# BSPD.net
KiCad netlist of a schematic drawn in EAGLE
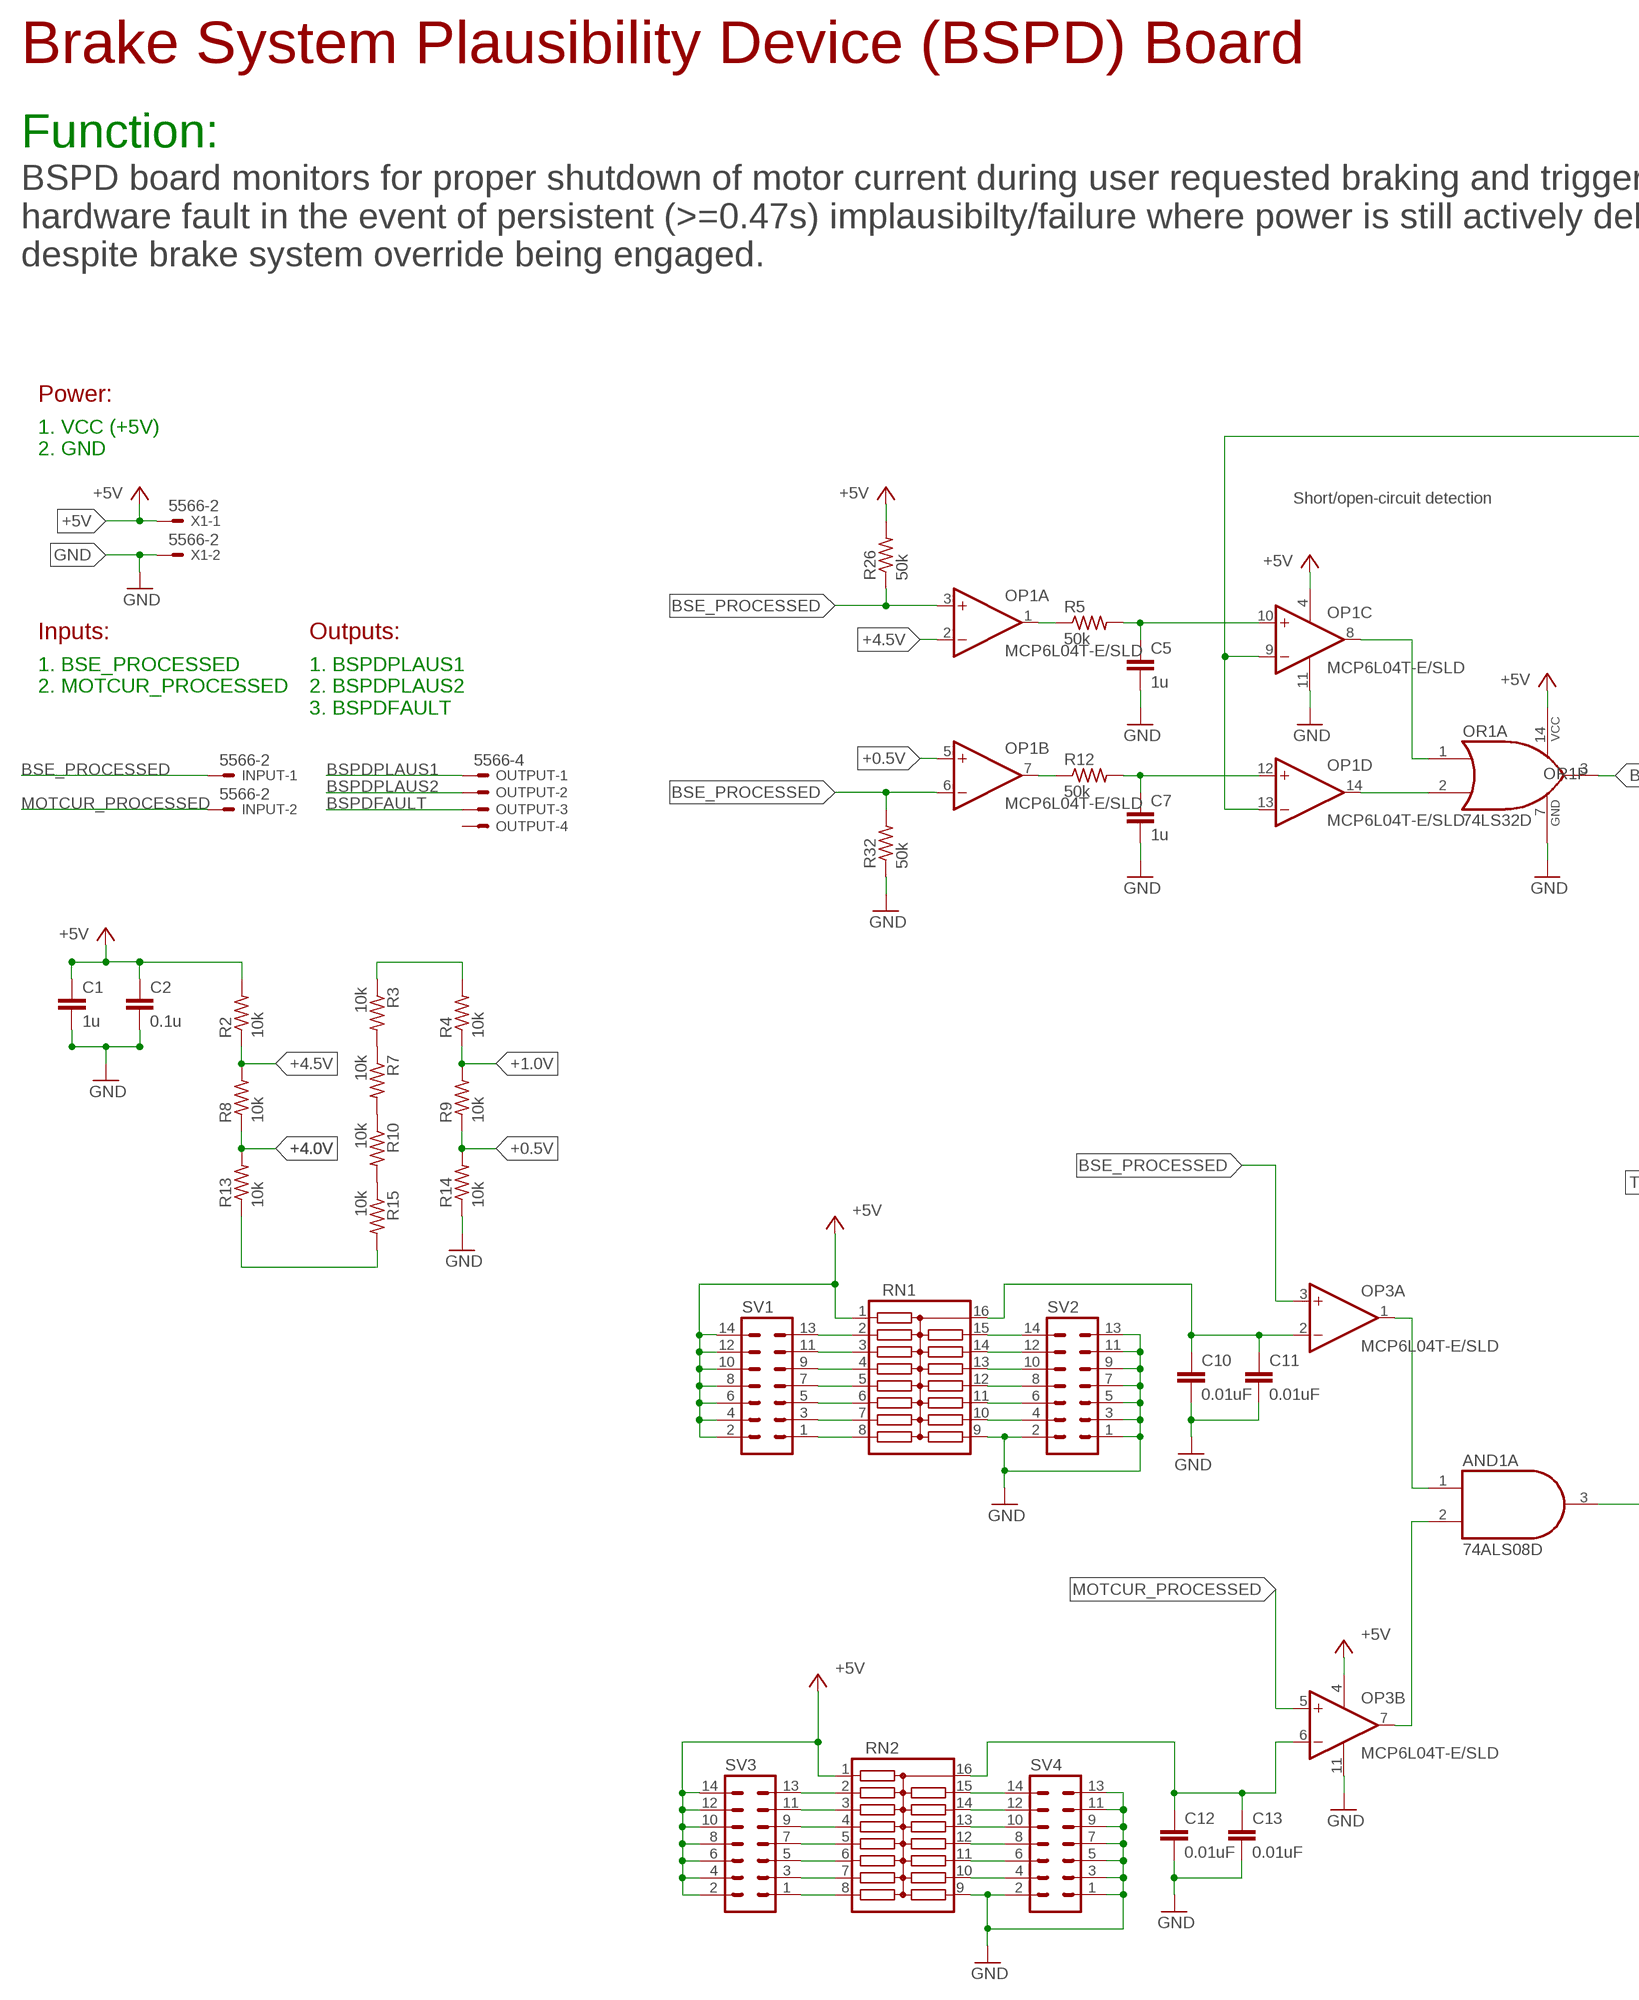
[diagram p0: schematic, sheet 1, part 1 of 2]
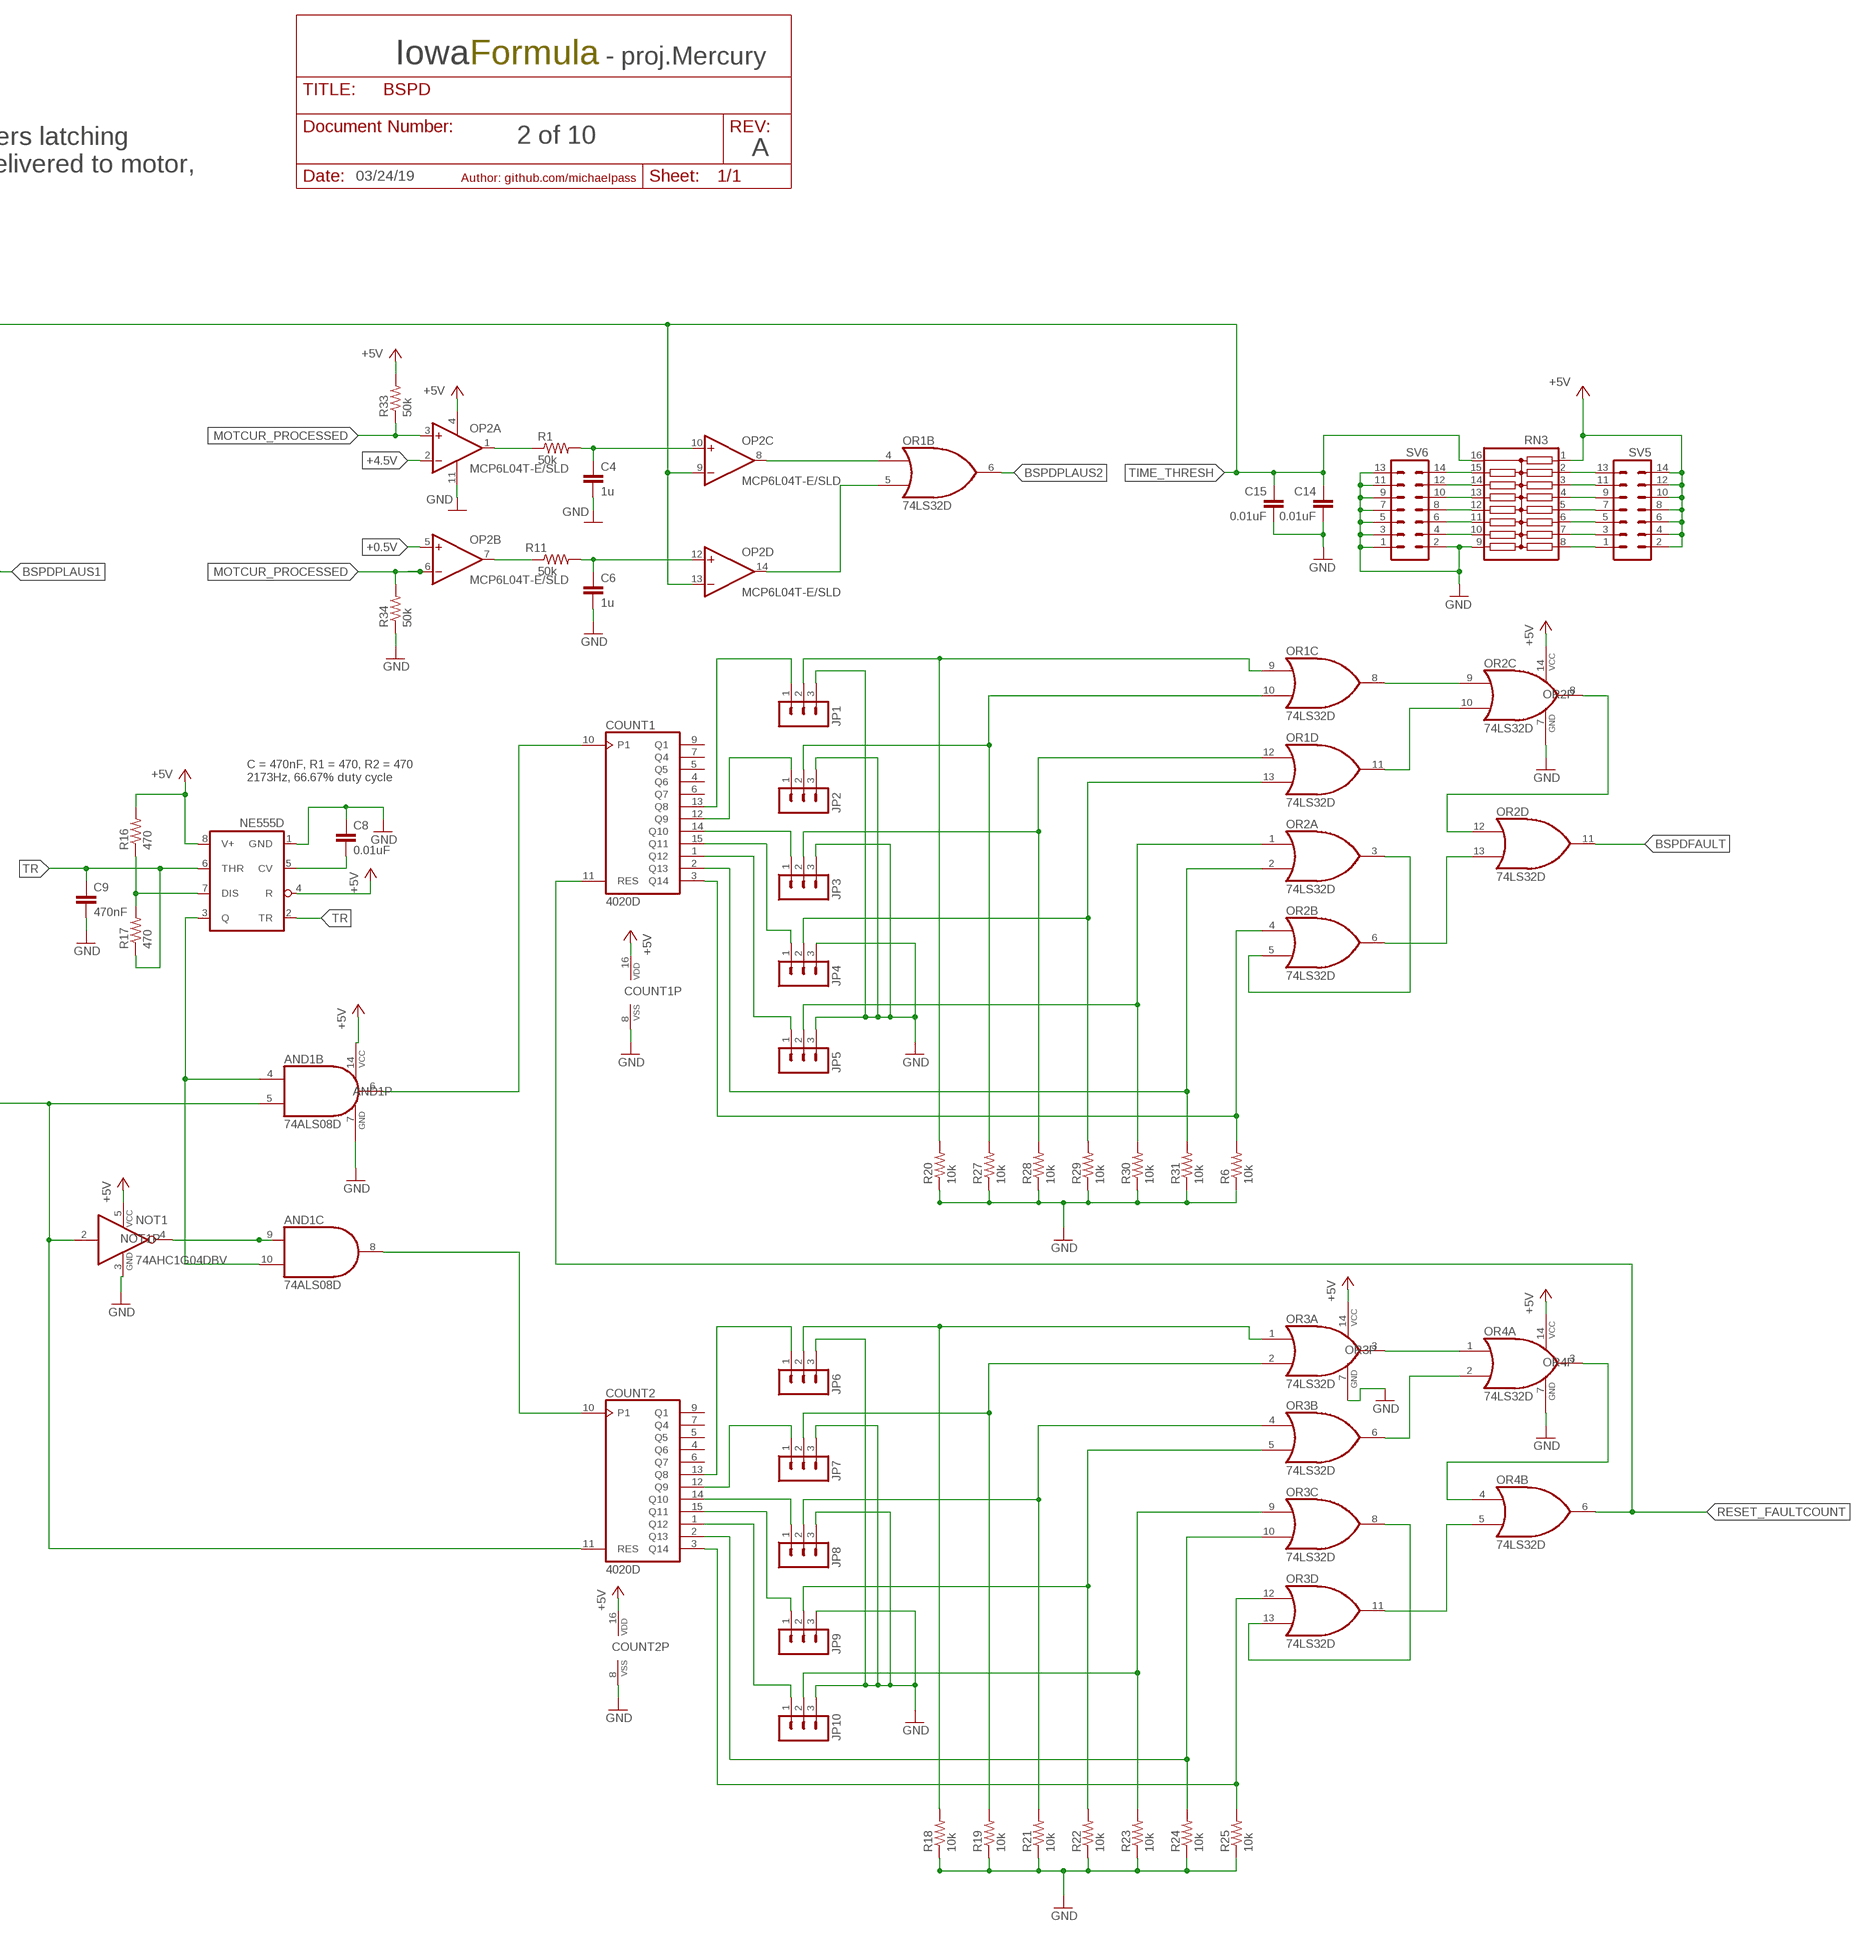
[diagram p1: schematic, sheet 1, part 2 of 2]

(export (version "E")
  (design (tool "Eeschema 10.0.6"))
  (components
    (comp (ref "AND1")
      (value "74ALS08D")
      (footprint "eagle-import:SO14")
      (libsource (lib "eagle-import") (part "7408DALS"))
    )
    (comp (ref "C1")
      (value "1u")
      (footprint "eagle-import:C0805")
      (libsource (lib "eagle-import") (part "C-EUC0805"))
    )
    (comp (ref "C2")
      (value "0.1u")
      (footprint "eagle-import:C0805")
      (libsource (lib "eagle-import") (part "C-EUC0805"))
    )
    (comp (ref "C4")
      (value "1u")
      (footprint "eagle-import:C0805")
      (libsource (lib "eagle-import") (part "C-EUC0805"))
    )
    (comp (ref "C5")
      (value "1u")
      (footprint "eagle-import:C0805")
      (libsource (lib "eagle-import") (part "C-EUC0805"))
    )
    (comp (ref "C6")
      (value "1u")
      (footprint "eagle-import:C0805")
      (libsource (lib "eagle-import") (part "C-EUC0805"))
    )
    (comp (ref "C7")
      (value "1u")
      (footprint "eagle-import:C0805")
      (libsource (lib "eagle-import") (part "C-EUC0805"))
    )
    (comp (ref "C8")
      (value "0.01uF")
      (footprint "eagle-import:C0805")
      (libsource (lib "eagle-import") (part "C-EUC0805"))
    )
    (comp (ref "C9")
      (value "470nF")
      (footprint "eagle-import:C0805")
      (libsource (lib "eagle-import") (part "C-EUC0805"))
    )
    (comp (ref "C10")
      (value "0.01uF")
      (footprint "eagle-import:C0805")
      (libsource (lib "eagle-import") (part "C-EUC0805"))
    )
    (comp (ref "C11")
      (value "0.01uF")
      (footprint "eagle-import:C0805")
      (libsource (lib "eagle-import") (part "C-EUC0805"))
    )
    (comp (ref "C12")
      (value "0.01uF")
      (footprint "eagle-import:C0805")
      (libsource (lib "eagle-import") (part "C-EUC0805"))
    )
    (comp (ref "C13")
      (value "0.01uF")
      (footprint "eagle-import:C0805")
      (libsource (lib "eagle-import") (part "C-EUC0805"))
    )
    (comp (ref "C14")
      (value "0.01uF")
      (footprint "eagle-import:C0805")
      (libsource (lib "eagle-import") (part "C-EUC0805"))
    )
    (comp (ref "C15")
      (value "0.01uF")
      (footprint "eagle-import:C0805")
      (libsource (lib "eagle-import") (part "C-EUC0805"))
    )
    (comp (ref "COUNT1")
      (value "4020D")
      (footprint "eagle-import:SO16")
      (libsource (lib "eagle-import") (part "4020D"))
    )
    (comp (ref "COUNT2")
      (value "4020D")
      (footprint "eagle-import:SO16")
      (libsource (lib "eagle-import") (part "4020D"))
    )
    (comp (ref "INPUT")
      (value "5566-2")
      (footprint "eagle-import:5566-2")
      (fields (field (name "MF") "MOLEX"))
      (libsource (lib "eagle-import") (part "5566-2"))
    )
    (comp (ref "JP1")
      (value "MA03-1")
      (footprint "eagle-import:MA03-1")
      (libsource (lib "eagle-import") (part "MA03-1"))
    )
    (comp (ref "JP2")
      (value "MA03-1")
      (footprint "eagle-import:MA03-1")
      (libsource (lib "eagle-import") (part "MA03-1"))
    )
    (comp (ref "JP3")
      (value "MA03-1")
      (footprint "eagle-import:MA03-1")
      (libsource (lib "eagle-import") (part "MA03-1"))
    )
    (comp (ref "JP4")
      (value "MA03-1")
      (footprint "eagle-import:MA03-1")
      (libsource (lib "eagle-import") (part "MA03-1"))
    )
    (comp (ref "JP5")
      (value "MA03-1")
      (footprint "eagle-import:MA03-1")
      (libsource (lib "eagle-import") (part "MA03-1"))
    )
    (comp (ref "JP6")
      (value "MA03-1")
      (footprint "eagle-import:MA03-1")
      (libsource (lib "eagle-import") (part "MA03-1"))
    )
    (comp (ref "JP7")
      (value "MA03-1")
      (footprint "eagle-import:MA03-1")
      (libsource (lib "eagle-import") (part "MA03-1"))
    )
    (comp (ref "JP8")
      (value "MA03-1")
      (footprint "eagle-import:MA03-1")
      (libsource (lib "eagle-import") (part "MA03-1"))
    )
    (comp (ref "JP9")
      (value "MA03-1")
      (footprint "eagle-import:MA03-1")
      (libsource (lib "eagle-import") (part "MA03-1"))
    )
    (comp (ref "JP10")
      (value "MA03-1")
      (footprint "eagle-import:MA03-1")
      (libsource (lib "eagle-import") (part "MA03-1"))
    )
    (comp (ref "NE555D")
      (value "NE555D")
      (footprint "eagle-import:SO08")
      (libsource (lib "eagle-import") (part "555DNE"))
    )
    (comp (ref "NOT1")
      (value "74AHC1G04DBV")
      (footprint "eagle-import:SOT23-5")
      (libsource (lib "eagle-import") (part "741G04DBVAHC"))
    )
    (comp (ref "OP1")
      (value "MCP6L04T-E/SLD")
      (footprint "eagle-import:SO14")
      (libsource (lib "eagle-import") (part "MCP6L04T-E/SLD"))
    )
    (comp (ref "OP2")
      (value "MCP6L04T-E/SLD")
      (footprint "eagle-import:SO14")
      (libsource (lib "eagle-import") (part "MCP6L04T-E/SLD"))
    )
    (comp (ref "OP3")
      (value "MCP6L04T-E/SLD")
      (footprint "eagle-import:SO14")
      (libsource (lib "eagle-import") (part "MCP6L04T-E/SLD"))
    )
    (comp (ref "OR1")
      (value "74LS32D")
      (footprint "eagle-import:SO14")
      (fields (field (name "SPICEPREFIX") "J"))
      (libsource (lib "eagle-import") (part "7432DLS"))
    )
    (comp (ref "OR2")
      (value "74LS32D")
      (footprint "eagle-import:SO14")
      (libsource (lib "eagle-import") (part "7432DLS"))
    )
    (comp (ref "OR3")
      (value "74LS32D")
      (footprint "eagle-import:SO14")
      (libsource (lib "eagle-import") (part "7432DLS"))
    )
    (comp (ref "OR4")
      (value "74LS32D")
      (footprint "eagle-import:SO14")
      (libsource (lib "eagle-import") (part "7432DLS"))
    )
    (comp (ref "OUTPUT")
      (value "5566-4")
      (footprint "eagle-import:5566-4")
      (fields (field (name "MF") "MOLEX"))
      (libsource (lib "eagle-import") (part "5566-4"))
    )
    (comp (ref "R1")
      (value "50k")
      (footprint "eagle-import:R0805")
      (libsource (lib "eagle-import") (part "R-US_R0805"))
    )
    (comp (ref "R2")
      (value "10k")
      (footprint "eagle-import:R0805")
      (libsource (lib "eagle-import") (part "R-US_R0805"))
    )
    (comp (ref "R3")
      (value "10k")
      (footprint "eagle-import:R0805")
      (libsource (lib "eagle-import") (part "R-US_R0805"))
    )
    (comp (ref "R4")
      (value "10k")
      (footprint "eagle-import:R0805")
      (libsource (lib "eagle-import") (part "R-US_R0805"))
    )
    (comp (ref "R5")
      (value "50k")
      (footprint "eagle-import:R0805")
      (libsource (lib "eagle-import") (part "R-US_R0805"))
    )
    (comp (ref "R6")
      (value "10k")
      (footprint "eagle-import:R0805")
      (libsource (lib "eagle-import") (part "R-US_R0805"))
    )
    (comp (ref "R7")
      (value "10k")
      (footprint "eagle-import:R0805")
      (libsource (lib "eagle-import") (part "R-US_R0805"))
    )
    (comp (ref "R8")
      (value "10k")
      (footprint "eagle-import:R0805")
      (libsource (lib "eagle-import") (part "R-US_R0805"))
    )
    (comp (ref "R9")
      (value "10k")
      (footprint "eagle-import:R0805")
      (libsource (lib "eagle-import") (part "R-US_R0805"))
    )
    (comp (ref "R10")
      (value "10k")
      (footprint "eagle-import:R0805")
      (libsource (lib "eagle-import") (part "R-US_R0805"))
    )
    (comp (ref "R11")
      (value "50k")
      (footprint "eagle-import:R0805")
      (libsource (lib "eagle-import") (part "R-US_R0805"))
    )
    (comp (ref "R12")
      (value "50k")
      (footprint "eagle-import:R0805")
      (libsource (lib "eagle-import") (part "R-US_R0805"))
    )
    (comp (ref "R13")
      (value "10k")
      (footprint "eagle-import:R0805")
      (libsource (lib "eagle-import") (part "R-US_R0805"))
    )
    (comp (ref "R14")
      (value "10k")
      (footprint "eagle-import:R0805")
      (libsource (lib "eagle-import") (part "R-US_R0805"))
    )
    (comp (ref "R15")
      (value "10k")
      (footprint "eagle-import:R0805")
      (libsource (lib "eagle-import") (part "R-US_R0805"))
    )
    (comp (ref "R16")
      (value "470")
      (footprint "eagle-import:R0805")
      (libsource (lib "eagle-import") (part "R-US_R0805"))
    )
    (comp (ref "R17")
      (value "470")
      (footprint "eagle-import:R0805")
      (libsource (lib "eagle-import") (part "R-US_R0805"))
    )
    (comp (ref "R18")
      (value "10k")
      (footprint "eagle-import:R0805")
      (libsource (lib "eagle-import") (part "R-US_R0805"))
    )
    (comp (ref "R19")
      (value "10k")
      (footprint "eagle-import:R0805")
      (libsource (lib "eagle-import") (part "R-US_R0805"))
    )
    (comp (ref "R20")
      (value "10k")
      (footprint "eagle-import:R0805")
      (libsource (lib "eagle-import") (part "R-US_R0805"))
    )
    (comp (ref "R21")
      (value "10k")
      (footprint "eagle-import:R0805")
      (libsource (lib "eagle-import") (part "R-US_R0805"))
    )
    (comp (ref "R22")
      (value "10k")
      (footprint "eagle-import:R0805")
      (libsource (lib "eagle-import") (part "R-US_R0805"))
    )
    (comp (ref "R23")
      (value "10k")
      (footprint "eagle-import:R0805")
      (libsource (lib "eagle-import") (part "R-US_R0805"))
    )
    (comp (ref "R24")
      (value "10k")
      (footprint "eagle-import:R0805")
      (libsource (lib "eagle-import") (part "R-US_R0805"))
    )
    (comp (ref "R25")
      (value "10k")
      (footprint "eagle-import:R0805")
      (libsource (lib "eagle-import") (part "R-US_R0805"))
    )
    (comp (ref "R26")
      (value "50k")
      (footprint "eagle-import:R0805")
      (libsource (lib "eagle-import") (part "R-US_R0805"))
    )
    (comp (ref "R27")
      (value "10k")
      (footprint "eagle-import:R0805")
      (libsource (lib "eagle-import") (part "R-US_R0805"))
    )
    (comp (ref "R28")
      (value "10k")
      (footprint "eagle-import:R0805")
      (libsource (lib "eagle-import") (part "R-US_R0805"))
    )
    (comp (ref "R29")
      (value "10k")
      (footprint "eagle-import:R0805")
      (libsource (lib "eagle-import") (part "R-US_R0805"))
    )
    (comp (ref "R30")
      (value "10k")
      (footprint "eagle-import:R0805")
      (libsource (lib "eagle-import") (part "R-US_R0805"))
    )
    (comp (ref "R31")
      (value "10k")
      (footprint "eagle-import:R0805")
      (libsource (lib "eagle-import") (part "R-US_R0805"))
    )
    (comp (ref "R32")
      (value "50k")
      (footprint "eagle-import:R0805")
      (libsource (lib "eagle-import") (part "R-US_R0805"))
    )
    (comp (ref "R33")
      (value "50k")
      (footprint "eagle-import:R0805")
      (libsource (lib "eagle-import") (part "R-US_R0805"))
    )
    (comp (ref "R34")
      (value "50k")
      (footprint "eagle-import:R0805")
      (libsource (lib "eagle-import") (part "R-US_R0805"))
    )
    (comp (ref "RN1")
      (value "15RSOMC")
      (footprint "eagle-import:SOMC16")
      (fields (field (name "MPN") "SOMC160115R0GDC"))
      (libsource (lib "eagle-import") (part "15RSOMC"))
    )
    (comp (ref "RN2")
      (value "15RSOMC")
      (footprint "eagle-import:SOMC16")
      (fields (field (name "MPN") "SOMC160115R0GDC"))
      (libsource (lib "eagle-import") (part "15RSOMC"))
    )
    (comp (ref "RN3")
      (value "15RSOMC")
      (footprint "eagle-import:SOMC16")
      (fields (field (name "MPN") "SOMC160115R0GDC"))
      (libsource (lib "eagle-import") (part "15RSOMC"))
    )
    (comp (ref "SV1")
      (value "MA07-2")
      (footprint "eagle-import:MA07-2")
      (libsource (lib "eagle-import") (part "MA07-2"))
    )
    (comp (ref "SV2")
      (value "MA07-2")
      (footprint "eagle-import:MA07-2")
      (libsource (lib "eagle-import") (part "MA07-2"))
    )
    (comp (ref "SV3")
      (value "MA07-2")
      (footprint "eagle-import:MA07-2")
      (libsource (lib "eagle-import") (part "MA07-2"))
    )
    (comp (ref "SV4")
      (value "MA07-2")
      (footprint "eagle-import:MA07-2")
      (libsource (lib "eagle-import") (part "MA07-2"))
    )
    (comp (ref "SV5")
      (value "MA07-2")
      (footprint "eagle-import:MA07-2")
      (libsource (lib "eagle-import") (part "MA07-2"))
    )
    (comp (ref "SV6")
      (value "MA07-2")
      (footprint "eagle-import:MA07-2")
      (libsource (lib "eagle-import") (part "MA07-2"))
    )
    (comp (ref "X1")
      (value "5566-2")
      (footprint "eagle-import:5566-2")
      (fields (field (name "MF") "MOLEX"))
      (libsource (lib "eagle-import") (part "5566-2"))
    )
  )
  (nets
    (net (code "1") (name "+0.5V") (class "Default")
      (node (ref "OP1") (pin "5") (pinfunction "+IN_5") (pintype "input"))
      (node (ref "OP2") (pin "5") (pinfunction "+IN_5") (pintype "input"))
      (node (ref "R14") (pin "2") (pinfunction "2_2") (pintype "passive"))
      (node (ref "R9") (pin "1") (pinfunction "1_1") (pintype "passive"))
    )
    (net (code "2") (name "+1.0V") (class "Default")
      (node (ref "R4") (pin "1") (pinfunction "1_1") (pintype "passive"))
      (node (ref "R9") (pin "2") (pinfunction "2_2") (pintype "passive"))
    )
    (net (code "3") (name "+4.0V") (class "Default")
      (node (ref "R13") (pin "2") (pinfunction "2_2") (pintype "passive"))
      (node (ref "R8") (pin "1") (pinfunction "1_1") (pintype "passive"))
    )
    (net (code "4") (name "+4.5V") (class "Default")
      (node (ref "OP1") (pin "2") (pinfunction "-IN_2") (pintype "input"))
      (node (ref "OP2") (pin "2") (pinfunction "-IN_2") (pintype "input"))
      (node (ref "R2") (pin "1") (pinfunction "1_1") (pintype "passive"))
      (node (ref "R8") (pin "2") (pinfunction "2_2") (pintype "passive"))
    )
    (net (code "5") (name "+5V") (class "Default")
      (node (ref "AND1") (pin "14") (pinfunction "VCC_14") (pintype "power_in"))
      (node (ref "C1") (pin "1") (pinfunction "1_1") (pintype "passive"))
      (node (ref "C2") (pin "1") (pinfunction "1_1") (pintype "passive"))
      (node (ref "COUNT1") (pin "16") (pinfunction "VDD_16") (pintype "power_in"))
      (node (ref "COUNT2") (pin "16") (pinfunction "VDD_16") (pintype "power_in"))
      (node (ref "NE555D") (pin "4") (pinfunction "R_4") (pintype "input"))
      (node (ref "NE555D") (pin "8") (pinfunction "V+_8") (pintype "power_in"))
      (node (ref "NOT1") (pin "5") (pinfunction "VCC_5") (pintype "power_in"))
      (node (ref "OP1") (pin "4") (pinfunction "V+_4") (pintype "power_in"))
      (node (ref "OP2") (pin "4") (pinfunction "V+_4") (pintype "power_in"))
      (node (ref "OP3") (pin "4") (pinfunction "V+_4") (pintype "power_in"))
      (node (ref "OR1") (pin "14") (pinfunction "VCC_14") (pintype "power_in"))
      (node (ref "OR2") (pin "14") (pinfunction "VCC_14") (pintype "power_in"))
      (node (ref "OR3") (pin "14") (pinfunction "VCC_14") (pintype "power_in"))
      (node (ref "OR4") (pin "14") (pinfunction "VCC_14") (pintype "power_in"))
      (node (ref "R16") (pin "2") (pinfunction "2_2") (pintype "passive"))
      (node (ref "R2") (pin "2") (pinfunction "2_2") (pintype "passive"))
      (node (ref "R26") (pin "2") (pinfunction "2_2") (pintype "passive"))
      (node (ref "R33") (pin "2") (pinfunction "2_2") (pintype "passive"))
      (node (ref "RN1") (pin "1") (pinfunction "1_1") (pintype "passive"))
      (node (ref "RN2") (pin "1") (pinfunction "1_1") (pintype "passive"))
      (node (ref "RN3") (pin "1") (pinfunction "1_1") (pintype "passive"))
      (node (ref "SV1") (pin "10") (pinfunction "10_10") (pintype "passive"))
      (node (ref "SV1") (pin "12") (pinfunction "12_12") (pintype "passive"))
      (node (ref "SV1") (pin "14") (pinfunction "14_14") (pintype "passive"))
      (node (ref "SV1") (pin "2") (pinfunction "2_2") (pintype "passive"))
      (node (ref "SV1") (pin "4") (pinfunction "4_4") (pintype "passive"))
      (node (ref "SV1") (pin "6") (pinfunction "6_6") (pintype "passive"))
      (node (ref "SV1") (pin "8") (pinfunction "8_8") (pintype "passive"))
      (node (ref "SV3") (pin "10") (pinfunction "10_10") (pintype "passive"))
      (node (ref "SV3") (pin "12") (pinfunction "12_12") (pintype "passive"))
      (node (ref "SV3") (pin "14") (pinfunction "14_14") (pintype "passive"))
      (node (ref "SV3") (pin "2") (pinfunction "2_2") (pintype "passive"))
      (node (ref "SV3") (pin "4") (pinfunction "4_4") (pintype "passive"))
      (node (ref "SV3") (pin "6") (pinfunction "6_6") (pintype "passive"))
      (node (ref "SV3") (pin "8") (pinfunction "8_8") (pintype "passive"))
      (node (ref "SV5") (pin "10") (pinfunction "10_10") (pintype "passive"))
      (node (ref "SV5") (pin "12") (pinfunction "12_12") (pintype "passive"))
      (node (ref "SV5") (pin "14") (pinfunction "14_14") (pintype "passive"))
      (node (ref "SV5") (pin "2") (pinfunction "2_2") (pintype "passive"))
      (node (ref "SV5") (pin "4") (pinfunction "4_4") (pintype "passive"))
      (node (ref "SV5") (pin "6") (pinfunction "6_6") (pintype "passive"))
      (node (ref "SV5") (pin "8") (pinfunction "8_8") (pintype "passive"))
      (node (ref "X1") (pin "1") (pinfunction "S_1") (pintype "passive"))
    )
    (net (code "6") (name "BSE_PROCESSED") (class "Default")
      (node (ref "INPUT") (pin "1") (pinfunction "S_1") (pintype "passive"))
      (node (ref "OP1") (pin "3") (pinfunction "+IN_3") (pintype "input"))
      (node (ref "OP1") (pin "6") (pinfunction "-IN_6") (pintype "input"))
      (node (ref "OP3") (pin "3") (pinfunction "+IN_3") (pintype "input"))
      (node (ref "R26") (pin "1") (pinfunction "1_1") (pintype "passive"))
      (node (ref "R32") (pin "2") (pinfunction "2_2") (pintype "passive"))
    )
    (net (code "7") (name "BSPDFAULT") (class "Default")
      (node (ref "OR2") (pin "11") (pinfunction "O_11") (pintype "output"))
      (node (ref "OUTPUT") (pin "3") (pinfunction "S_3") (pintype "passive"))
    )
    (net (code "8") (name "BSPDPLAUS1") (class "Default")
      (node (ref "OR1") (pin "3") (pinfunction "O_3") (pintype "output"))
      (node (ref "OUTPUT") (pin "1") (pinfunction "S_1") (pintype "passive"))
    )
    (net (code "9") (name "BSPDPLAUS2") (class "Default")
      (node (ref "OR1") (pin "6") (pinfunction "O_6") (pintype "output"))
      (node (ref "OUTPUT") (pin "2") (pinfunction "S_2") (pintype "passive"))
    )
    (net (code "10") (name "GND") (class "Default")
      (node (ref "AND1") (pin "7") (pinfunction "GND_7") (pintype "power_in"))
      (node (ref "C1") (pin "2") (pinfunction "2_2") (pintype "passive"))
      (node (ref "C10") (pin "2") (pinfunction "2_2") (pintype "passive"))
      (node (ref "C11") (pin "2") (pinfunction "2_2") (pintype "passive"))
      (node (ref "C12") (pin "2") (pinfunction "2_2") (pintype "passive"))
      (node (ref "C13") (pin "2") (pinfunction "2_2") (pintype "passive"))
      (node (ref "C14") (pin "2") (pinfunction "2_2") (pintype "passive"))
      (node (ref "C15") (pin "2") (pinfunction "2_2") (pintype "passive"))
      (node (ref "C2") (pin "2") (pinfunction "2_2") (pintype "passive"))
      (node (ref "C4") (pin "2") (pinfunction "2_2") (pintype "passive"))
      (node (ref "C5") (pin "2") (pinfunction "2_2") (pintype "passive"))
      (node (ref "C6") (pin "2") (pinfunction "2_2") (pintype "passive"))
      (node (ref "C7") (pin "2") (pinfunction "2_2") (pintype "passive"))
      (node (ref "C8") (pin "1") (pinfunction "1_1") (pintype "passive"))
      (node (ref "C9") (pin "2") (pinfunction "2_2") (pintype "passive"))
      (node (ref "COUNT1") (pin "8") (pinfunction "VSS_8") (pintype "power_in"))
      (node (ref "COUNT2") (pin "8") (pinfunction "VSS_8") (pintype "power_in"))
      (node (ref "JP1") (pin "3") (pinfunction "3_3") (pintype "passive"))
      (node (ref "JP10") (pin "3") (pinfunction "3_3") (pintype "passive"))
      (node (ref "JP2") (pin "3") (pinfunction "3_3") (pintype "passive"))
      (node (ref "JP3") (pin "3") (pinfunction "3_3") (pintype "passive"))
      (node (ref "JP4") (pin "3") (pinfunction "3_3") (pintype "passive"))
      (node (ref "JP5") (pin "3") (pinfunction "3_3") (pintype "passive"))
      (node (ref "JP6") (pin "3") (pinfunction "3_3") (pintype "passive"))
      (node (ref "JP7") (pin "3") (pinfunction "3_3") (pintype "passive"))
      (node (ref "JP8") (pin "3") (pinfunction "3_3") (pintype "passive"))
      (node (ref "JP9") (pin "3") (pinfunction "3_3") (pintype "passive"))
      (node (ref "NE555D") (pin "1") (pinfunction "GND_1") (pintype "power_in"))
      (node (ref "NOT1") (pin "3") (pinfunction "GND_3") (pintype "power_in"))
      (node (ref "OP1") (pin "11") (pinfunction "V-_11") (pintype "power_in"))
      (node (ref "OP2") (pin "11") (pinfunction "V-_11") (pintype "power_in"))
      (node (ref "OP3") (pin "11") (pinfunction "V-_11") (pintype "power_in"))
      (node (ref "OR1") (pin "7") (pinfunction "GND_7") (pintype "power_in"))
      (node (ref "OR2") (pin "7") (pinfunction "GND_7") (pintype "power_in"))
      (node (ref "OR3") (pin "7") (pinfunction "GND_7") (pintype "power_in"))
      (node (ref "OR4") (pin "7") (pinfunction "GND_7") (pintype "power_in"))
      (node (ref "R14") (pin "1") (pinfunction "1_1") (pintype "passive"))
      (node (ref "R18") (pin "1") (pinfunction "1_1") (pintype "passive"))
      (node (ref "R19") (pin "1") (pinfunction "1_1") (pintype "passive"))
      (node (ref "R20") (pin "1") (pinfunction "1_1") (pintype "passive"))
      (node (ref "R21") (pin "1") (pinfunction "1_1") (pintype "passive"))
      (node (ref "R22") (pin "1") (pinfunction "1_1") (pintype "passive"))
      (node (ref "R23") (pin "1") (pinfunction "1_1") (pintype "passive"))
      (node (ref "R24") (pin "1") (pinfunction "1_1") (pintype "passive"))
      (node (ref "R25") (pin "1") (pinfunction "1_1") (pintype "passive"))
      (node (ref "R27") (pin "1") (pinfunction "1_1") (pintype "passive"))
      (node (ref "R28") (pin "1") (pinfunction "1_1") (pintype "passive"))
      (node (ref "R29") (pin "1") (pinfunction "1_1") (pintype "passive"))
      (node (ref "R30") (pin "1") (pinfunction "1_1") (pintype "passive"))
      (node (ref "R31") (pin "1") (pinfunction "1_1") (pintype "passive"))
      (node (ref "R32") (pin "1") (pinfunction "1_1") (pintype "passive"))
      (node (ref "R34") (pin "1") (pinfunction "1_1") (pintype "passive"))
      (node (ref "R6") (pin "1") (pinfunction "1_1") (pintype "passive"))
      (node (ref "RN1") (pin "9") (pinfunction "9_9") (pintype "passive"))
      (node (ref "RN2") (pin "9") (pinfunction "9_9") (pintype "passive"))
      (node (ref "RN3") (pin "9") (pinfunction "9_9") (pintype "passive"))
      (node (ref "SV2") (pin "1") (pinfunction "1_1") (pintype "passive"))
      (node (ref "SV2") (pin "11") (pinfunction "11_11") (pintype "passive"))
      (node (ref "SV2") (pin "13") (pinfunction "13_13") (pintype "passive"))
      (node (ref "SV2") (pin "2") (pinfunction "2_2") (pintype "passive"))
      (node (ref "SV2") (pin "3") (pinfunction "3_3") (pintype "passive"))
      (node (ref "SV2") (pin "5") (pinfunction "5_5") (pintype "passive"))
      (node (ref "SV2") (pin "7") (pinfunction "7_7") (pintype "passive"))
      (node (ref "SV2") (pin "9") (pinfunction "9_9") (pintype "passive"))
      (node (ref "SV4") (pin "1") (pinfunction "1_1") (pintype "passive"))
      (node (ref "SV4") (pin "11") (pinfunction "11_11") (pintype "passive"))
      (node (ref "SV4") (pin "13") (pinfunction "13_13") (pintype "passive"))
      (node (ref "SV4") (pin "2") (pinfunction "2_2") (pintype "passive"))
      (node (ref "SV4") (pin "3") (pinfunction "3_3") (pintype "passive"))
      (node (ref "SV4") (pin "5") (pinfunction "5_5") (pintype "passive"))
      (node (ref "SV4") (pin "7") (pinfunction "7_7") (pintype "passive"))
      (node (ref "SV4") (pin "9") (pinfunction "9_9") (pintype "passive"))
      (node (ref "SV6") (pin "1") (pinfunction "1_1") (pintype "passive"))
      (node (ref "SV6") (pin "11") (pinfunction "11_11") (pintype "passive"))
      (node (ref "SV6") (pin "13") (pinfunction "13_13") (pintype "passive"))
      (node (ref "SV6") (pin "2") (pinfunction "2_2") (pintype "passive"))
      (node (ref "SV6") (pin "3") (pinfunction "3_3") (pintype "passive"))
      (node (ref "SV6") (pin "5") (pinfunction "5_5") (pintype "passive"))
      (node (ref "SV6") (pin "7") (pinfunction "7_7") (pintype "passive"))
      (node (ref "SV6") (pin "9") (pinfunction "9_9") (pintype "passive"))
      (node (ref "X1") (pin "2") (pinfunction "S_2") (pintype "passive"))
    )
    (net (code "11") (name "MOTCUR_PROCESSED") (class "Default")
      (node (ref "INPUT") (pin "2") (pinfunction "S_2") (pintype "passive"))
      (node (ref "OP2") (pin "3") (pinfunction "+IN_3") (pintype "input"))
      (node (ref "OP2") (pin "6") (pinfunction "-IN_6") (pintype "input"))
      (node (ref "OP3") (pin "5") (pinfunction "+IN_5") (pintype "input"))
      (node (ref "R33") (pin "1") (pinfunction "1_1") (pintype "passive"))
      (node (ref "R34") (pin "2") (pinfunction "2_2") (pintype "passive"))
    )
    (net (code "12") (name "Net-(AND1A-I0)") (class "Default")
      (node (ref "AND1") (pin "1") (pinfunction "I0_1") (pintype "input"))
      (node (ref "OP3") (pin "1") (pinfunction "OUT_1") (pintype "output"))
    )
    (net (code "13") (name "Net-(AND1A-I1)") (class "Default")
      (node (ref "AND1") (pin "2") (pinfunction "I1_2") (pintype "input"))
      (node (ref "OP3") (pin "7") (pinfunction "OUT_7") (pintype "output"))
    )
    (net (code "14") (name "Net-(AND1A-O)") (class "Default")
      (node (ref "AND1") (pin "3") (pinfunction "O_3") (pintype "output"))
      (node (ref "AND1") (pin "5") (pinfunction "I1_5") (pintype "input"))
      (node (ref "COUNT2") (pin "11") (pinfunction "RES_11") (pintype "input"))
      (node (ref "NOT1") (pin "2") (pinfunction "I_2") (pintype "input"))
    )
    (net (code "15") (name "Net-(AND1B-I0)") (class "Default")
      (node (ref "AND1") (pin "10") (pinfunction "I1_10") (pintype "input"))
      (node (ref "AND1") (pin "4") (pinfunction "I0_4") (pintype "input"))
      (node (ref "NE555D") (pin "3") (pinfunction "Q_3") (pintype "output"))
    )
    (net (code "16") (name "Net-(AND1B-O)") (class "Default")
      (node (ref "AND1") (pin "6") (pinfunction "O_6") (pintype "output"))
      (node (ref "COUNT1") (pin "10") (pinfunction "P1_10") (pintype "input"))
    )
    (net (code "17") (name "Net-(AND1C-I0)") (class "Default")
      (node (ref "AND1") (pin "9") (pinfunction "I0_9") (pintype "input"))
      (node (ref "NOT1") (pin "4") (pinfunction "O_4") (pintype "output"))
    )
    (net (code "18") (name "Net-(AND1C-O)") (class "Default")
      (node (ref "AND1") (pin "8") (pinfunction "O_8") (pintype "output"))
      (node (ref "COUNT2") (pin "10") (pinfunction "P1_10") (pintype "input"))
    )
    (net (code "19") (name "Net-(COUNT1A-Q8)") (class "Default")
      (node (ref "COUNT1") (pin "13") (pinfunction "Q8_13") (pintype "output"))
      (node (ref "JP1") (pin "1") (pinfunction "1_1") (pintype "passive"))
    )
    (net (code "20") (name "Net-(COUNT1A-Q9)") (class "Default")
      (node (ref "COUNT1") (pin "12") (pinfunction "Q9_12") (pintype "output"))
      (node (ref "JP2") (pin "1") (pinfunction "1_1") (pintype "passive"))
    )
    (net (code "21") (name "Net-(COUNT1A-Q10)") (class "Default")
      (node (ref "COUNT1") (pin "14") (pinfunction "Q10_14") (pintype "output"))
      (node (ref "JP3") (pin "1") (pinfunction "1_1") (pintype "passive"))
    )
    (net (code "22") (name "Net-(COUNT1A-Q11)") (class "Default")
      (node (ref "COUNT1") (pin "15") (pinfunction "Q11_15") (pintype "output"))
      (node (ref "JP4") (pin "1") (pinfunction "1_1") (pintype "passive"))
    )
    (net (code "23") (name "Net-(COUNT1A-Q12)") (class "Default")
      (node (ref "COUNT1") (pin "1") (pinfunction "Q12_1") (pintype "output"))
      (node (ref "JP5") (pin "1") (pinfunction "1_1") (pintype "passive"))
    )
    (net (code "24") (name "Net-(COUNT1A-Q13)") (class "Default")
      (node (ref "COUNT1") (pin "2") (pinfunction "Q13_2") (pintype "output"))
      (node (ref "OR2") (pin "2") (pinfunction "I1_2") (pintype "input"))
      (node (ref "R31") (pin "2") (pinfunction "2_2") (pintype "passive"))
    )
    (net (code "25") (name "Net-(COUNT1A-Q14)") (class "Default")
      (node (ref "COUNT1") (pin "3") (pinfunction "Q14_3") (pintype "output"))
      (node (ref "OR2") (pin "4") (pinfunction "I0_4") (pintype "input"))
      (node (ref "R6") (pin "2") (pinfunction "2_2") (pintype "passive"))
    )
    (net (code "26") (name "Net-(COUNT2A-Q8)") (class "Default")
      (node (ref "COUNT2") (pin "13") (pinfunction "Q8_13") (pintype "output"))
      (node (ref "JP6") (pin "1") (pinfunction "1_1") (pintype "passive"))
    )
    (net (code "27") (name "Net-(COUNT2A-Q9)") (class "Default")
      (node (ref "COUNT2") (pin "12") (pinfunction "Q9_12") (pintype "output"))
      (node (ref "JP7") (pin "1") (pinfunction "1_1") (pintype "passive"))
    )
    (net (code "28") (name "Net-(COUNT2A-Q10)") (class "Default")
      (node (ref "COUNT2") (pin "14") (pinfunction "Q10_14") (pintype "output"))
      (node (ref "JP8") (pin "1") (pinfunction "1_1") (pintype "passive"))
    )
    (net (code "29") (name "Net-(COUNT2A-Q11)") (class "Default")
      (node (ref "COUNT2") (pin "15") (pinfunction "Q11_15") (pintype "output"))
      (node (ref "JP9") (pin "1") (pinfunction "1_1") (pintype "passive"))
    )
    (net (code "30") (name "Net-(COUNT2A-Q12)") (class "Default")
      (node (ref "COUNT2") (pin "1") (pinfunction "Q12_1") (pintype "output"))
      (node (ref "JP10") (pin "1") (pinfunction "1_1") (pintype "passive"))
    )
    (net (code "31") (name "Net-(COUNT2A-Q13)") (class "Default")
      (node (ref "COUNT2") (pin "2") (pinfunction "Q13_2") (pintype "output"))
      (node (ref "OR3") (pin "10") (pinfunction "I1_10") (pintype "input"))
      (node (ref "R24") (pin "2") (pinfunction "2_2") (pintype "passive"))
    )
    (net (code "32") (name "Net-(COUNT2A-Q14)") (class "Default")
      (node (ref "COUNT2") (pin "3") (pinfunction "Q14_3") (pintype "output"))
      (node (ref "OR3") (pin "12") (pinfunction "I0_12") (pintype "input"))
      (node (ref "R25") (pin "2") (pinfunction "2_2") (pintype "passive"))
    )
    (net (code "33") (name "Net-(NE555D-CV)") (class "Default")
      (node (ref "C8") (pin "2") (pinfunction "2_2") (pintype "passive"))
      (node (ref "NE555D") (pin "5") (pinfunction "CV_5") (pintype "input"))
    )
    (net (code "34") (name "Net-(NE555D-DIS)") (class "Default")
      (node (ref "NE555D") (pin "7") (pinfunction "DIS_7") (pintype "input"))
      (node (ref "R16") (pin "1") (pinfunction "1_1") (pintype "passive"))
      (node (ref "R17") (pin "2") (pinfunction "2_2") (pintype "passive"))
    )
    (net (code "35") (name "Net-(OP1A-OUT)") (class "Default")
      (node (ref "OP1") (pin "1") (pinfunction "OUT_1") (pintype "output"))
      (node (ref "R5") (pin "1") (pinfunction "1_1") (pintype "passive"))
    )
    (net (code "36") (name "Net-(OP1B-OUT)") (class "Default")
      (node (ref "OP1") (pin "7") (pinfunction "OUT_7") (pintype "output"))
      (node (ref "R12") (pin "1") (pinfunction "1_1") (pintype "passive"))
    )
    (net (code "37") (name "Net-(OP1C-+IN)") (class "Default")
      (node (ref "C5") (pin "1") (pinfunction "1_1") (pintype "passive"))
      (node (ref "OP1") (pin "10") (pinfunction "+IN_10") (pintype "input"))
      (node (ref "R5") (pin "2") (pinfunction "2_2") (pintype "passive"))
    )
    (net (code "38") (name "Net-(OP1C-OUT)") (class "Default")
      (node (ref "OP1") (pin "8") (pinfunction "OUT_8") (pintype "output"))
      (node (ref "OR1") (pin "1") (pinfunction "I0_1") (pintype "input"))
    )
    (net (code "39") (name "Net-(OP1D-+IN)") (class "Default")
      (node (ref "C7") (pin "1") (pinfunction "1_1") (pintype "passive"))
      (node (ref "OP1") (pin "12") (pinfunction "+IN_12") (pintype "input"))
      (node (ref "R12") (pin "2") (pinfunction "2_2") (pintype "passive"))
    )
    (net (code "40") (name "Net-(OP1D-OUT)") (class "Default")
      (node (ref "OP1") (pin "14") (pinfunction "OUT_14") (pintype "output"))
      (node (ref "OR1") (pin "2") (pinfunction "I1_2") (pintype "input"))
    )
    (net (code "41") (name "Net-(OP2A-OUT)") (class "Default")
      (node (ref "OP2") (pin "1") (pinfunction "OUT_1") (pintype "output"))
      (node (ref "R1") (pin "1") (pinfunction "1_1") (pintype "passive"))
    )
    (net (code "42") (name "Net-(OP2B-OUT)") (class "Default")
      (node (ref "OP2") (pin "7") (pinfunction "OUT_7") (pintype "output"))
      (node (ref "R11") (pin "1") (pinfunction "1_1") (pintype "passive"))
    )
    (net (code "43") (name "Net-(OP2C-+IN)") (class "Default")
      (node (ref "C4") (pin "1") (pinfunction "1_1") (pintype "passive"))
      (node (ref "OP2") (pin "10") (pinfunction "+IN_10") (pintype "input"))
      (node (ref "R1") (pin "2") (pinfunction "2_2") (pintype "passive"))
    )
    (net (code "44") (name "Net-(OP2C-OUT)") (class "Default")
      (node (ref "OP2") (pin "8") (pinfunction "OUT_8") (pintype "output"))
      (node (ref "OR1") (pin "4") (pinfunction "I0_4") (pintype "input"))
    )
    (net (code "45") (name "Net-(OP2D-+IN)") (class "Default")
      (node (ref "C6") (pin "1") (pinfunction "1_1") (pintype "passive"))
      (node (ref "OP2") (pin "12") (pinfunction "+IN_12") (pintype "input"))
      (node (ref "R11") (pin "2") (pinfunction "2_2") (pintype "passive"))
    )
    (net (code "46") (name "Net-(OP2D-OUT)") (class "Default")
      (node (ref "OP2") (pin "14") (pinfunction "OUT_14") (pintype "output"))
      (node (ref "OR1") (pin "5") (pinfunction "I1_5") (pintype "input"))
    )
    (net (code "47") (name "Net-(OP3A--IN)") (class "Default")
      (node (ref "C10") (pin "1") (pinfunction "1_1") (pintype "passive"))
      (node (ref "C11") (pin "1") (pinfunction "1_1") (pintype "passive"))
      (node (ref "OP3") (pin "2") (pinfunction "-IN_2") (pintype "input"))
      (node (ref "RN1") (pin "16") (pinfunction "16_16") (pintype "passive"))
    )
    (net (code "48") (name "Net-(OP3B--IN)") (class "Default")
      (node (ref "C12") (pin "1") (pinfunction "1_1") (pintype "passive"))
      (node (ref "C13") (pin "1") (pinfunction "1_1") (pintype "passive"))
      (node (ref "OP3") (pin "6") (pinfunction "-IN_6") (pintype "input"))
      (node (ref "RN2") (pin "16") (pinfunction "16_16") (pintype "passive"))
    )
    (net (code "49") (name "Net-(OR1C-I0)") (class "Default")
      (node (ref "JP1") (pin "2") (pinfunction "2_2") (pintype "passive"))
      (node (ref "OR1") (pin "9") (pinfunction "I0_9") (pintype "input"))
      (node (ref "R20") (pin "2") (pinfunction "2_2") (pintype "passive"))
    )
    (net (code "50") (name "Net-(OR1C-I1)") (class "Default")
      (node (ref "JP2") (pin "2") (pinfunction "2_2") (pintype "passive"))
      (node (ref "OR1") (pin "10") (pinfunction "I1_10") (pintype "input"))
      (node (ref "R27") (pin "2") (pinfunction "2_2") (pintype "passive"))
    )
    (net (code "51") (name "Net-(OR1C-O)") (class "Default")
      (node (ref "OR1") (pin "8") (pinfunction "O_8") (pintype "output"))
      (node (ref "OR2") (pin "9") (pinfunction "I0_9") (pintype "input"))
    )
    (net (code "52") (name "Net-(OR1D-I0)") (class "Default")
      (node (ref "JP3") (pin "2") (pinfunction "2_2") (pintype "passive"))
      (node (ref "OR1") (pin "12") (pinfunction "I0_12") (pintype "input"))
      (node (ref "R28") (pin "2") (pinfunction "2_2") (pintype "passive"))
    )
    (net (code "53") (name "Net-(OR1D-I1)") (class "Default")
      (node (ref "JP4") (pin "2") (pinfunction "2_2") (pintype "passive"))
      (node (ref "OR1") (pin "13") (pinfunction "I1_13") (pintype "input"))
      (node (ref "R29") (pin "2") (pinfunction "2_2") (pintype "passive"))
    )
    (net (code "54") (name "Net-(OR1D-O)") (class "Default")
      (node (ref "OR1") (pin "11") (pinfunction "O_11") (pintype "output"))
      (node (ref "OR2") (pin "10") (pinfunction "I1_10") (pintype "input"))
    )
    (net (code "55") (name "Net-(OR2A-I0)") (class "Default")
      (node (ref "JP5") (pin "2") (pinfunction "2_2") (pintype "passive"))
      (node (ref "OR2") (pin "1") (pinfunction "I0_1") (pintype "input"))
      (node (ref "R30") (pin "2") (pinfunction "2_2") (pintype "passive"))
    )
    (net (code "56") (name "Net-(OR2A-O)") (class "Default")
      (node (ref "OR2") (pin "3") (pinfunction "O_3") (pintype "output"))
      (node (ref "OR2") (pin "5") (pinfunction "I1_5") (pintype "input"))
    )
    (net (code "57") (name "Net-(OR2B-O)") (class "Default")
      (node (ref "OR2") (pin "13") (pinfunction "I1_13") (pintype "input"))
      (node (ref "OR2") (pin "6") (pinfunction "O_6") (pintype "output"))
    )
    (net (code "58") (name "Net-(OR2C-O)") (class "Default")
      (node (ref "OR2") (pin "12") (pinfunction "I0_12") (pintype "input"))
      (node (ref "OR2") (pin "8") (pinfunction "O_8") (pintype "output"))
    )
    (net (code "59") (name "Net-(OR3A-I0)") (class "Default")
      (node (ref "JP6") (pin "2") (pinfunction "2_2") (pintype "passive"))
      (node (ref "OR3") (pin "1") (pinfunction "I0_1") (pintype "input"))
      (node (ref "R18") (pin "2") (pinfunction "2_2") (pintype "passive"))
    )
    (net (code "60") (name "Net-(OR3A-I1)") (class "Default")
      (node (ref "JP7") (pin "2") (pinfunction "2_2") (pintype "passive"))
      (node (ref "OR3") (pin "2") (pinfunction "I1_2") (pintype "input"))
      (node (ref "R19") (pin "2") (pinfunction "2_2") (pintype "passive"))
    )
    (net (code "61") (name "Net-(OR3A-O)") (class "Default")
      (node (ref "OR3") (pin "3") (pinfunction "O_3") (pintype "output"))
      (node (ref "OR4") (pin "1") (pinfunction "I0_1") (pintype "input"))
    )
    (net (code "62") (name "Net-(OR3B-I0)") (class "Default")
      (node (ref "JP8") (pin "2") (pinfunction "2_2") (pintype "passive"))
      (node (ref "OR3") (pin "4") (pinfunction "I0_4") (pintype "input"))
      (node (ref "R21") (pin "2") (pinfunction "2_2") (pintype "passive"))
    )
    (net (code "63") (name "Net-(OR3B-I1)") (class "Default")
      (node (ref "JP9") (pin "2") (pinfunction "2_2") (pintype "passive"))
      (node (ref "OR3") (pin "5") (pinfunction "I1_5") (pintype "input"))
      (node (ref "R22") (pin "2") (pinfunction "2_2") (pintype "passive"))
    )
    (net (code "64") (name "Net-(OR3B-O)") (class "Default")
      (node (ref "OR3") (pin "6") (pinfunction "O_6") (pintype "output"))
      (node (ref "OR4") (pin "2") (pinfunction "I1_2") (pintype "input"))
    )
    (net (code "65") (name "Net-(OR3C-I0)") (class "Default")
      (node (ref "JP10") (pin "2") (pinfunction "2_2") (pintype "passive"))
      (node (ref "OR3") (pin "9") (pinfunction "I0_9") (pintype "input"))
      (node (ref "R23") (pin "2") (pinfunction "2_2") (pintype "passive"))
    )
    (net (code "66") (name "Net-(OR3C-O)") (class "Default")
      (node (ref "OR3") (pin "13") (pinfunction "I1_13") (pintype "input"))
      (node (ref "OR3") (pin "8") (pinfunction "O_8") (pintype "output"))
    )
    (net (code "67") (name "Net-(OR3D-O)") (class "Default")
      (node (ref "OR3") (pin "11") (pinfunction "O_11") (pintype "output"))
      (node (ref "OR4") (pin "5") (pinfunction "I1_5") (pintype "input"))
    )
    (net (code "68") (name "Net-(OR4A-O)") (class "Default")
      (node (ref "OR4") (pin "3") (pinfunction "O_3") (pintype "output"))
      (node (ref "OR4") (pin "4") (pinfunction "I0_4") (pintype "input"))
    )
    (net (code "69") (name "Net-(R3-Pad1)") (class "Default")
      (node (ref "R3") (pin "1") (pinfunction "1_1") (pintype "passive"))
      (node (ref "R4") (pin "2") (pinfunction "2_2") (pintype "passive"))
    )
    (net (code "70") (name "Net-(R3-Pad2)") (class "Default")
      (node (ref "R3") (pin "2") (pinfunction "2_2") (pintype "passive"))
      (node (ref "R7") (pin "1") (pinfunction "1_1") (pintype "passive"))
    )
    (net (code "71") (name "Net-(R10-Pad1)") (class "Default")
      (node (ref "R10") (pin "1") (pinfunction "1_1") (pintype "passive"))
      (node (ref "R7") (pin "2") (pinfunction "2_2") (pintype "passive"))
    )
    (net (code "72") (name "Net-(R10-Pad2)") (class "Default")
      (node (ref "R10") (pin "2") (pinfunction "2_2") (pintype "passive"))
      (node (ref "R15") (pin "1") (pinfunction "1_1") (pintype "passive"))
    )
    (net (code "73") (name "Net-(R13-Pad1)") (class "Default")
      (node (ref "R13") (pin "1") (pinfunction "1_1") (pintype "passive"))
      (node (ref "R15") (pin "2") (pinfunction "2_2") (pintype "passive"))
    )
    (net (code "74") (name "Net-(RN1-Pad2)") (class "Default")
      (node (ref "RN1") (pin "2") (pinfunction "2_2") (pintype "passive"))
      (node (ref "SV1") (pin "13") (pinfunction "13_13") (pintype "passive"))
    )
    (net (code "75") (name "Net-(RN1-Pad3)") (class "Default")
      (node (ref "RN1") (pin "3") (pinfunction "3_3") (pintype "passive"))
      (node (ref "SV1") (pin "11") (pinfunction "11_11") (pintype "passive"))
    )
    (net (code "76") (name "Net-(RN1-Pad4)") (class "Default")
      (node (ref "RN1") (pin "4") (pinfunction "4_4") (pintype "passive"))
      (node (ref "SV1") (pin "9") (pinfunction "9_9") (pintype "passive"))
    )
    (net (code "77") (name "Net-(RN1-Pad5)") (class "Default")
      (node (ref "RN1") (pin "5") (pinfunction "5_5") (pintype "passive"))
      (node (ref "SV1") (pin "7") (pinfunction "7_7") (pintype "passive"))
    )
    (net (code "78") (name "Net-(RN1-Pad6)") (class "Default")
      (node (ref "RN1") (pin "6") (pinfunction "6_6") (pintype "passive"))
      (node (ref "SV1") (pin "5") (pinfunction "5_5") (pintype "passive"))
    )
    (net (code "79") (name "Net-(RN1-Pad7)") (class "Default")
      (node (ref "RN1") (pin "7") (pinfunction "7_7") (pintype "passive"))
      (node (ref "SV1") (pin "3") (pinfunction "3_3") (pintype "passive"))
    )
    (net (code "80") (name "Net-(RN1-Pad8)") (class "Default")
      (node (ref "RN1") (pin "8") (pinfunction "8_8") (pintype "passive"))
      (node (ref "SV1") (pin "1") (pinfunction "1_1") (pintype "passive"))
    )
    (net (code "81") (name "Net-(RN1-Pad10)") (class "Default")
      (node (ref "RN1") (pin "10") (pinfunction "10_10") (pintype "passive"))
      (node (ref "SV2") (pin "4") (pinfunction "4_4") (pintype "passive"))
    )
    (net (code "82") (name "Net-(RN1-Pad11)") (class "Default")
      (node (ref "RN1") (pin "11") (pinfunction "11_11") (pintype "passive"))
      (node (ref "SV2") (pin "6") (pinfunction "6_6") (pintype "passive"))
    )
    (net (code "83") (name "Net-(RN1-Pad12)") (class "Default")
      (node (ref "RN1") (pin "12") (pinfunction "12_12") (pintype "passive"))
      (node (ref "SV2") (pin "8") (pinfunction "8_8") (pintype "passive"))
    )
    (net (code "84") (name "Net-(RN1-Pad13)") (class "Default")
      (node (ref "RN1") (pin "13") (pinfunction "13_13") (pintype "passive"))
      (node (ref "SV2") (pin "10") (pinfunction "10_10") (pintype "passive"))
    )
    (net (code "85") (name "Net-(RN1-Pad14)") (class "Default")
      (node (ref "RN1") (pin "14") (pinfunction "14_14") (pintype "passive"))
      (node (ref "SV2") (pin "12") (pinfunction "12_12") (pintype "passive"))
    )
    (net (code "86") (name "Net-(RN1-Pad15)") (class "Default")
      (node (ref "RN1") (pin "15") (pinfunction "15_15") (pintype "passive"))
      (node (ref "SV2") (pin "14") (pinfunction "14_14") (pintype "passive"))
    )
    (net (code "87") (name "Net-(RN2-Pad2)") (class "Default")
      (node (ref "RN2") (pin "2") (pinfunction "2_2") (pintype "passive"))
      (node (ref "SV3") (pin "13") (pinfunction "13_13") (pintype "passive"))
    )
    (net (code "88") (name "Net-(RN2-Pad3)") (class "Default")
      (node (ref "RN2") (pin "3") (pinfunction "3_3") (pintype "passive"))
      (node (ref "SV3") (pin "11") (pinfunction "11_11") (pintype "passive"))
    )
    (net (code "89") (name "Net-(RN2-Pad4)") (class "Default")
      (node (ref "RN2") (pin "4") (pinfunction "4_4") (pintype "passive"))
      (node (ref "SV3") (pin "9") (pinfunction "9_9") (pintype "passive"))
    )
    (net (code "90") (name "Net-(RN2-Pad5)") (class "Default")
      (node (ref "RN2") (pin "5") (pinfunction "5_5") (pintype "passive"))
      (node (ref "SV3") (pin "7") (pinfunction "7_7") (pintype "passive"))
    )
    (net (code "91") (name "Net-(RN2-Pad6)") (class "Default")
      (node (ref "RN2") (pin "6") (pinfunction "6_6") (pintype "passive"))
      (node (ref "SV3") (pin "5") (pinfunction "5_5") (pintype "passive"))
    )
    (net (code "92") (name "Net-(RN2-Pad7)") (class "Default")
      (node (ref "RN2") (pin "7") (pinfunction "7_7") (pintype "passive"))
      (node (ref "SV3") (pin "3") (pinfunction "3_3") (pintype "passive"))
    )
    (net (code "93") (name "Net-(RN2-Pad8)") (class "Default")
      (node (ref "RN2") (pin "8") (pinfunction "8_8") (pintype "passive"))
      (node (ref "SV3") (pin "1") (pinfunction "1_1") (pintype "passive"))
    )
    (net (code "94") (name "Net-(RN2-Pad10)") (class "Default")
      (node (ref "RN2") (pin "10") (pinfunction "10_10") (pintype "passive"))
      (node (ref "SV4") (pin "4") (pinfunction "4_4") (pintype "passive"))
    )
    (net (code "95") (name "Net-(RN2-Pad11)") (class "Default")
      (node (ref "RN2") (pin "11") (pinfunction "11_11") (pintype "passive"))
      (node (ref "SV4") (pin "6") (pinfunction "6_6") (pintype "passive"))
    )
    (net (code "96") (name "Net-(RN2-Pad12)") (class "Default")
      (node (ref "RN2") (pin "12") (pinfunction "12_12") (pintype "passive"))
      (node (ref "SV4") (pin "8") (pinfunction "8_8") (pintype "passive"))
    )
    (net (code "97") (name "Net-(RN2-Pad13)") (class "Default")
      (node (ref "RN2") (pin "13") (pinfunction "13_13") (pintype "passive"))
      (node (ref "SV4") (pin "10") (pinfunction "10_10") (pintype "passive"))
    )
    (net (code "98") (name "Net-(RN2-Pad14)") (class "Default")
      (node (ref "RN2") (pin "14") (pinfunction "14_14") (pintype "passive"))
      (node (ref "SV4") (pin "12") (pinfunction "12_12") (pintype "passive"))
    )
    (net (code "99") (name "Net-(RN2-Pad15)") (class "Default")
      (node (ref "RN2") (pin "15") (pinfunction "15_15") (pintype "passive"))
      (node (ref "SV4") (pin "14") (pinfunction "14_14") (pintype "passive"))
    )
    (net (code "100") (name "Net-(RN3-Pad2)") (class "Default")
      (node (ref "RN3") (pin "2") (pinfunction "2_2") (pintype "passive"))
      (node (ref "SV5") (pin "13") (pinfunction "13_13") (pintype "passive"))
    )
    (net (code "101") (name "Net-(RN3-Pad3)") (class "Default")
      (node (ref "RN3") (pin "3") (pinfunction "3_3") (pintype "passive"))
      (node (ref "SV5") (pin "11") (pinfunction "11_11") (pintype "passive"))
    )
    (net (code "102") (name "Net-(RN3-Pad4)") (class "Default")
      (node (ref "RN3") (pin "4") (pinfunction "4_4") (pintype "passive"))
      (node (ref "SV5") (pin "9") (pinfunction "9_9") (pintype "passive"))
    )
    (net (code "103") (name "Net-(RN3-Pad5)") (class "Default")
      (node (ref "RN3") (pin "5") (pinfunction "5_5") (pintype "passive"))
      (node (ref "SV5") (pin "7") (pinfunction "7_7") (pintype "passive"))
    )
    (net (code "104") (name "Net-(RN3-Pad6)") (class "Default")
      (node (ref "RN3") (pin "6") (pinfunction "6_6") (pintype "passive"))
      (node (ref "SV5") (pin "5") (pinfunction "5_5") (pintype "passive"))
    )
    (net (code "105") (name "Net-(RN3-Pad7)") (class "Default")
      (node (ref "RN3") (pin "7") (pinfunction "7_7") (pintype "passive"))
      (node (ref "SV5") (pin "3") (pinfunction "3_3") (pintype "passive"))
    )
    (net (code "106") (name "Net-(RN3-Pad8)") (class "Default")
      (node (ref "RN3") (pin "8") (pinfunction "8_8") (pintype "passive"))
      (node (ref "SV5") (pin "1") (pinfunction "1_1") (pintype "passive"))
    )
    (net (code "107") (name "Net-(RN3-Pad10)") (class "Default")
      (node (ref "RN3") (pin "10") (pinfunction "10_10") (pintype "passive"))
      (node (ref "SV6") (pin "4") (pinfunction "4_4") (pintype "passive"))
    )
    (net (code "108") (name "Net-(RN3-Pad11)") (class "Default")
      (node (ref "RN3") (pin "11") (pinfunction "11_11") (pintype "passive"))
      (node (ref "SV6") (pin "6") (pinfunction "6_6") (pintype "passive"))
    )
    (net (code "109") (name "Net-(RN3-Pad12)") (class "Default")
      (node (ref "RN3") (pin "12") (pinfunction "12_12") (pintype "passive"))
      (node (ref "SV6") (pin "8") (pinfunction "8_8") (pintype "passive"))
    )
    (net (code "110") (name "Net-(RN3-Pad13)") (class "Default")
      (node (ref "RN3") (pin "13") (pinfunction "13_13") (pintype "passive"))
      (node (ref "SV6") (pin "10") (pinfunction "10_10") (pintype "passive"))
    )
    (net (code "111") (name "Net-(RN3-Pad14)") (class "Default")
      (node (ref "RN3") (pin "14") (pinfunction "14_14") (pintype "passive"))
      (node (ref "SV6") (pin "12") (pinfunction "12_12") (pintype "passive"))
    )
    (net (code "112") (name "Net-(RN3-Pad15)") (class "Default")
      (node (ref "RN3") (pin "15") (pinfunction "15_15") (pintype "passive"))
      (node (ref "SV6") (pin "14") (pinfunction "14_14") (pintype "passive"))
    )
    (net (code "113") (name "RESET_FAULTCOUNT") (class "Default")
      (node (ref "COUNT1") (pin "11") (pinfunction "RES_11") (pintype "input"))
      (node (ref "OR4") (pin "6") (pinfunction "O_6") (pintype "output"))
    )
    (net (code "114") (name "TIME_THRESH") (class "Default")
      (node (ref "C14") (pin "1") (pinfunction "1_1") (pintype "passive"))
      (node (ref "C15") (pin "1") (pinfunction "1_1") (pintype "passive"))
      (node (ref "OP1") (pin "13") (pinfunction "-IN_13") (pintype "input"))
      (node (ref "OP1") (pin "9") (pinfunction "-IN_9") (pintype "input"))
      (node (ref "OP2") (pin "13") (pinfunction "-IN_13") (pintype "input"))
      (node (ref "OP2") (pin "9") (pinfunction "-IN_9") (pintype "input"))
      (node (ref "RN3") (pin "16") (pinfunction "16_16") (pintype "passive"))
    )
    (net (code "115") (name "TR") (class "Default")
      (node (ref "C9") (pin "1") (pinfunction "1_1") (pintype "passive"))
      (node (ref "NE555D") (pin "2") (pinfunction "TR_2") (pintype "input"))
      (node (ref "NE555D") (pin "6") (pinfunction "THR_6") (pintype "input"))
      (node (ref "R17") (pin "1") (pinfunction "1_1") (pintype "passive"))
    )
    (net (code "116") (name "unconnected-(COUNT1A-Q1-Pad9)") (class "Default")
      (node (ref "COUNT1") (pin "9") (pinfunction "Q1_9") (pintype "output"))
    )
    (net (code "117") (name "unconnected-(COUNT1A-Q4-Pad7)") (class "Default")
      (node (ref "COUNT1") (pin "7") (pinfunction "Q4_7") (pintype "output"))
    )
    (net (code "118") (name "unconnected-(COUNT1A-Q5-Pad5)") (class "Default")
      (node (ref "COUNT1") (pin "5") (pinfunction "Q5_5") (pintype "output"))
    )
    (net (code "119") (name "unconnected-(COUNT1A-Q6-Pad4)") (class "Default")
      (node (ref "COUNT1") (pin "4") (pinfunction "Q6_4") (pintype "output"))
    )
    (net (code "120") (name "unconnected-(COUNT1A-Q7-Pad6)") (class "Default")
      (node (ref "COUNT1") (pin "6") (pinfunction "Q7_6") (pintype "output"))
    )
    (net (code "121") (name "unconnected-(COUNT2A-Q1-Pad9)") (class "Default")
      (node (ref "COUNT2") (pin "9") (pinfunction "Q1_9") (pintype "output"))
    )
    (net (code "122") (name "unconnected-(COUNT2A-Q4-Pad7)") (class "Default")
      (node (ref "COUNT2") (pin "7") (pinfunction "Q4_7") (pintype "output"))
    )
    (net (code "123") (name "unconnected-(COUNT2A-Q5-Pad5)") (class "Default")
      (node (ref "COUNT2") (pin "5") (pinfunction "Q5_5") (pintype "output"))
    )
    (net (code "124") (name "unconnected-(COUNT2A-Q6-Pad4)") (class "Default")
      (node (ref "COUNT2") (pin "4") (pinfunction "Q6_4") (pintype "output"))
    )
    (net (code "125") (name "unconnected-(COUNT2A-Q7-Pad6)") (class "Default")
      (node (ref "COUNT2") (pin "6") (pinfunction "Q7_6") (pintype "output"))
    )
    (net (code "126") (name "unconnected-(OUTPUTD-S-Pad4)") (class "Default")
      (node (ref "OUTPUT") (pin "4") (pinfunction "S_4") (pintype "passive"))
    )
  )
)
